# badge.net
KiCad netlist of a schematic drawn in EAGLE
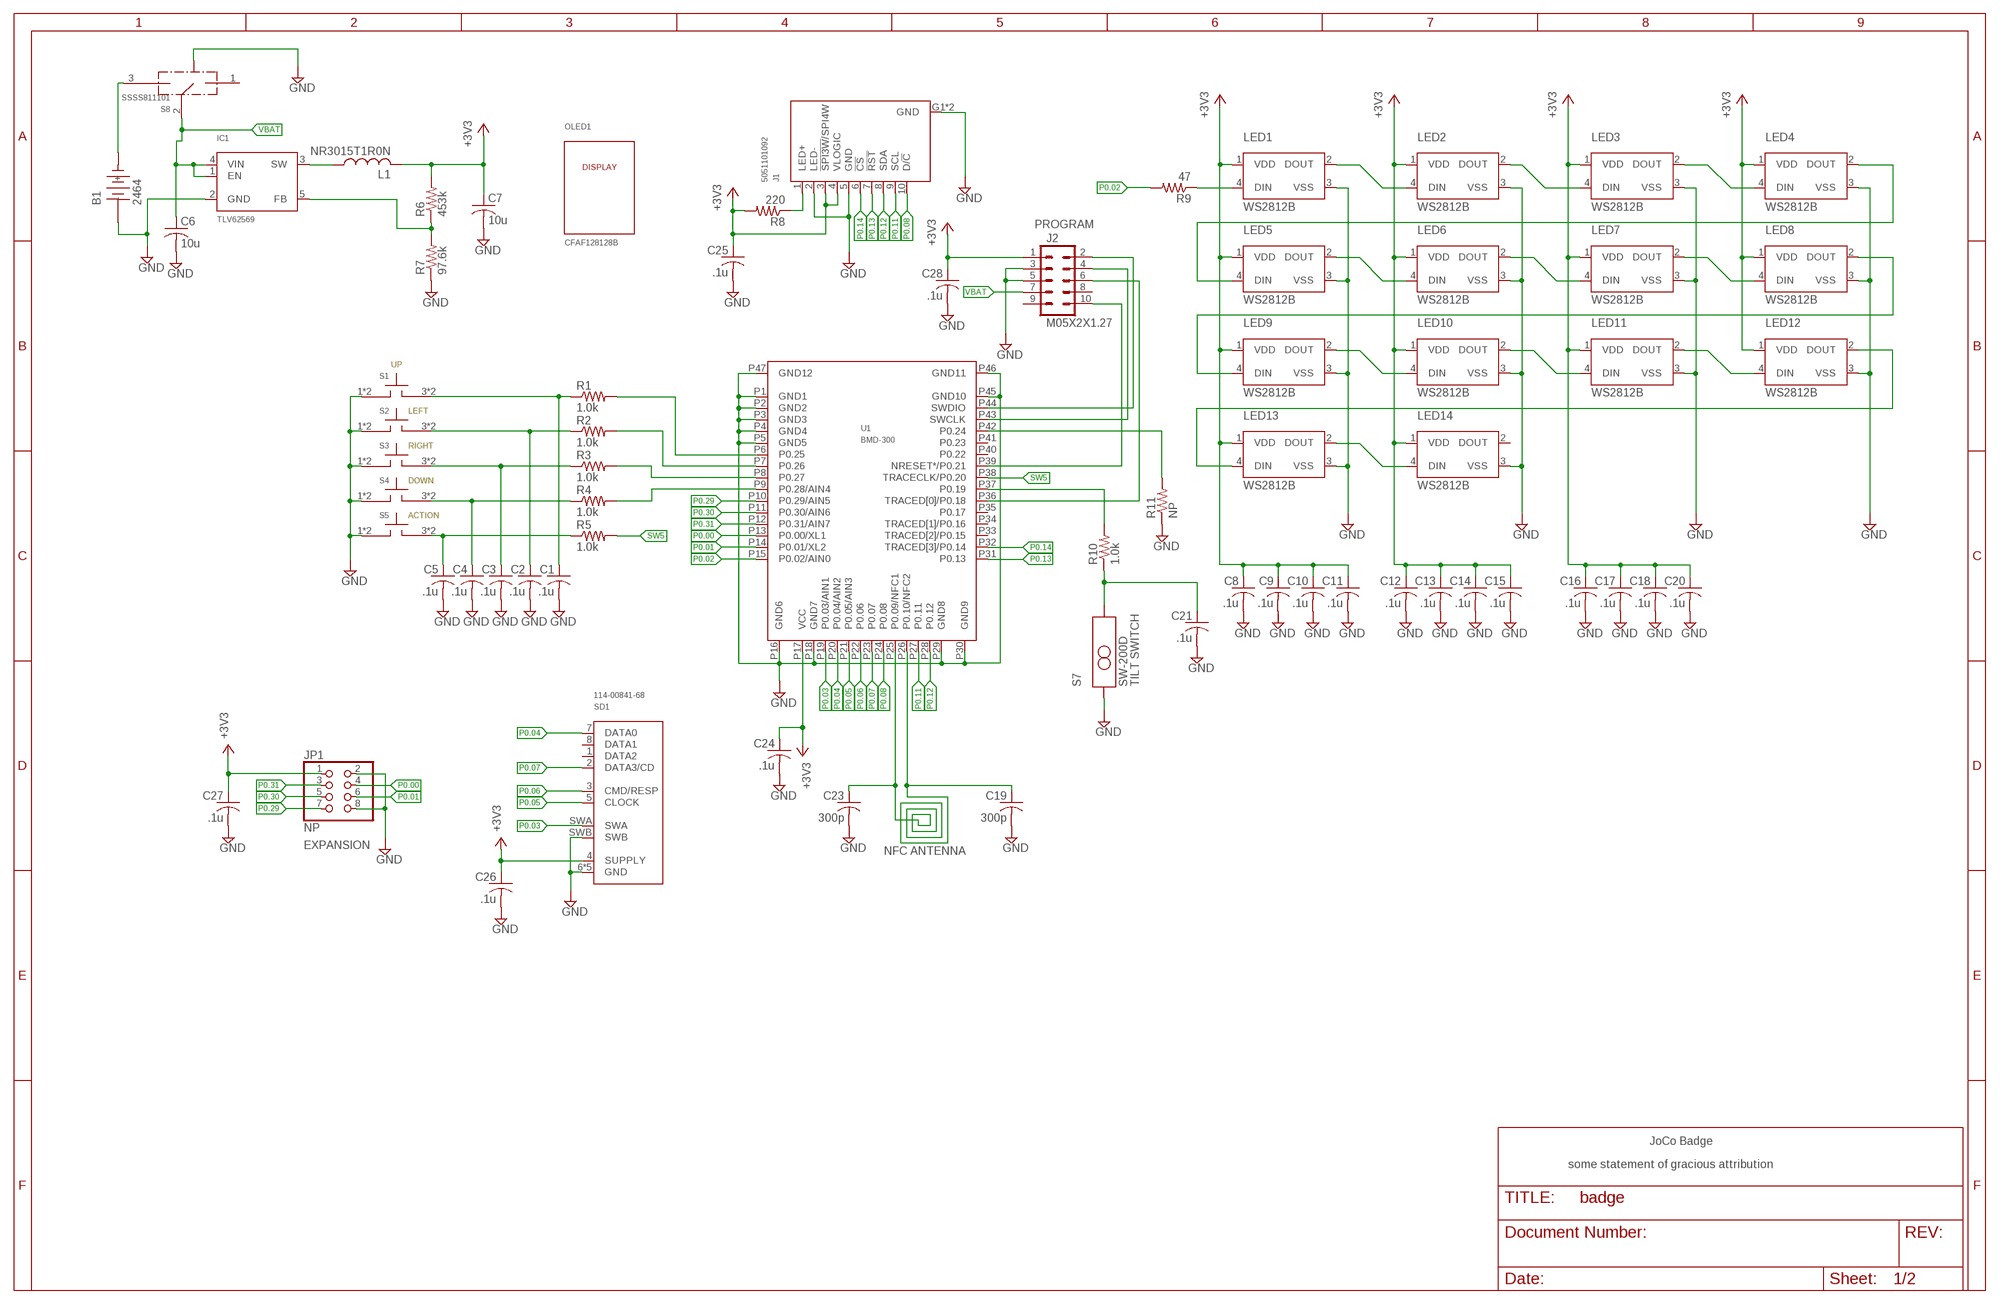
[diagram p0: schematic, sheet 1]
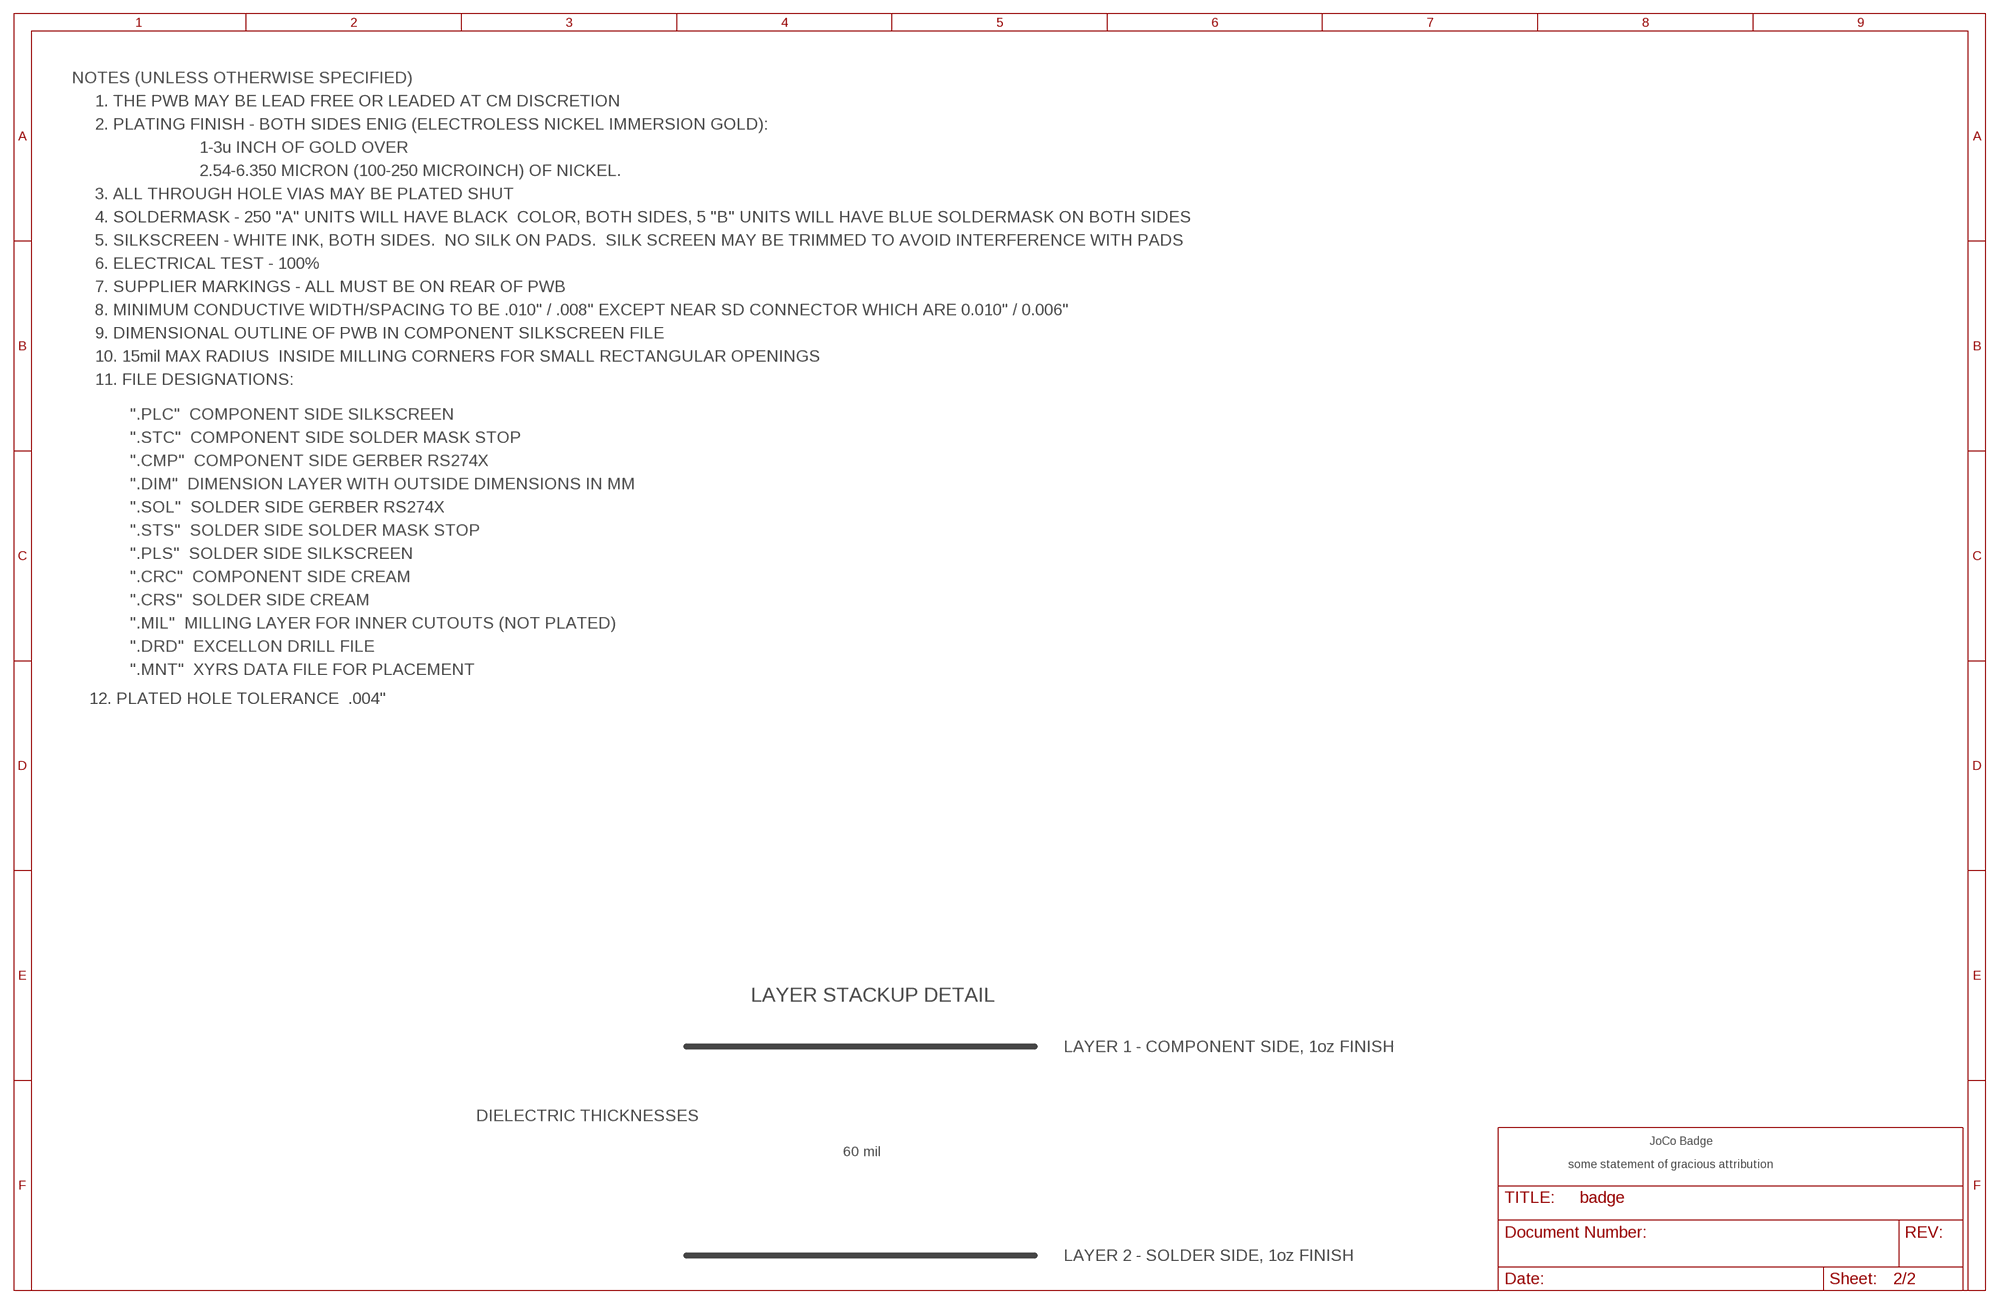
[diagram p1: schematic, sheet 2]

(export (version "E")
  (design (tool "Eeschema 10.0.6"))
  (components
    (comp (ref "B1")
      (value "2464")
      (footprint "eagle-import:2464")
      (libsource (lib "eagle-import") (part "2464"))
    )
    (comp (ref "C1")
      (value ".1u")
      (footprint "eagle-import:C0402K")
      (libsource (lib "eagle-import") (part "C-USC0402K"))
    )
    (comp (ref "C2")
      (value ".1u")
      (footprint "eagle-import:C0402K")
      (libsource (lib "eagle-import") (part "C-USC0402K"))
    )
    (comp (ref "C3")
      (value ".1u")
      (footprint "eagle-import:C0402K")
      (libsource (lib "eagle-import") (part "C-USC0402K"))
    )
    (comp (ref "C4")
      (value ".1u")
      (footprint "eagle-import:C0402K")
      (libsource (lib "eagle-import") (part "C-USC0402K"))
    )
    (comp (ref "C5")
      (value ".1u")
      (footprint "eagle-import:C0402K")
      (libsource (lib "eagle-import") (part "C-USC0402K"))
    )
    (comp (ref "C6")
      (value "10u")
      (footprint "eagle-import:C0805K")
      (fields (field (name "MPN") "JMK212BJ106KD-T"))
      (libsource (lib "eagle-import") (part "C-USC0805K"))
    )
    (comp (ref "C7")
      (value "10u")
      (footprint "eagle-import:C0805K")
      (fields (field (name "MPN") "JMK212BJ106KD-T"))
      (libsource (lib "eagle-import") (part "C-USC0805K"))
    )
    (comp (ref "C8")
      (value ".1u")
      (footprint "eagle-import:C0402K")
      (libsource (lib "eagle-import") (part "C-USC0402K"))
    )
    (comp (ref "C9")
      (value ".1u")
      (footprint "eagle-import:C0402K")
      (libsource (lib "eagle-import") (part "C-USC0402K"))
    )
    (comp (ref "C10")
      (value ".1u")
      (footprint "eagle-import:C0402K")
      (libsource (lib "eagle-import") (part "C-USC0402K"))
    )
    (comp (ref "C11")
      (value ".1u")
      (footprint "eagle-import:C0402K")
      (libsource (lib "eagle-import") (part "C-USC0402K"))
    )
    (comp (ref "C12")
      (value ".1u")
      (footprint "eagle-import:C0402K")
      (libsource (lib "eagle-import") (part "C-USC0402K"))
    )
    (comp (ref "C13")
      (value ".1u")
      (footprint "eagle-import:C0402K")
      (libsource (lib "eagle-import") (part "C-USC0402K"))
    )
    (comp (ref "C14")
      (value ".1u")
      (footprint "eagle-import:C0402K")
      (libsource (lib "eagle-import") (part "C-USC0402K"))
    )
    (comp (ref "C15")
      (value ".1u")
      (footprint "eagle-import:C0402K")
      (libsource (lib "eagle-import") (part "C-USC0402K"))
    )
    (comp (ref "C16")
      (value ".1u")
      (footprint "eagle-import:C0402K")
      (libsource (lib "eagle-import") (part "C-USC0402K"))
    )
    (comp (ref "C17")
      (value ".1u")
      (footprint "eagle-import:C0402K")
      (libsource (lib "eagle-import") (part "C-USC0402K"))
    )
    (comp (ref "C18")
      (value ".1u")
      (footprint "eagle-import:C0402K")
      (libsource (lib "eagle-import") (part "C-USC0402K"))
    )
    (comp (ref "C19")
      (value "300p")
      (footprint "eagle-import:C0603K")
      (libsource (lib "eagle-import") (part "C-USC0603K"))
    )
    (comp (ref "C20")
      (value ".1u")
      (footprint "eagle-import:C0402K")
      (libsource (lib "eagle-import") (part "C-USC0402K"))
    )
    (comp (ref "C21")
      (value ".1u")
      (footprint "eagle-import:C0402K")
      (libsource (lib "eagle-import") (part "C-USC0402K"))
    )
    (comp (ref "C23")
      (value "300p")
      (footprint "eagle-import:C0603K")
      (libsource (lib "eagle-import") (part "C-USC0603K"))
    )
    (comp (ref "C24")
      (value ".1u")
      (footprint "eagle-import:C0402K")
      (libsource (lib "eagle-import") (part "C-USC0402K"))
    )
    (comp (ref "C25")
      (value ".1u")
      (footprint "eagle-import:C0402K")
      (libsource (lib "eagle-import") (part "C-USC0402K"))
    )
    (comp (ref "C26")
      (value ".1u")
      (footprint "eagle-import:C0402K")
      (libsource (lib "eagle-import") (part "C-USC0402K"))
    )
    (comp (ref "C27")
      (value ".1u")
      (footprint "eagle-import:C0402K")
      (libsource (lib "eagle-import") (part "C-USC0402K"))
    )
    (comp (ref "C28")
      (value ".1u")
      (footprint "eagle-import:C0402K")
      (libsource (lib "eagle-import") (part "C-USC0402K"))
    )
    (comp (ref "IC1")
      (value "TLV62569")
      (footprint "eagle-import:DBV-5")
      (libsource (lib "eagle-import") (part "TLV62569"))
    )
    (comp (ref "J1")
      (value "5051101092")
      (footprint "eagle-import:5051101092")
      (libsource (lib "eagle-import") (part "5051101092"))
    )
    (comp (ref "J2")
      (value "M05X2X1.27")
      (footprint "eagle-import:2X5X1.27")
      (libsource (lib "eagle-import") (part "M05X2X1.27"))
    )
    (comp (ref "JP1")
      (value "NP")
      (footprint "eagle-import:2X04")
      (libsource (lib "eagle-import") (part "PINHD-2X4"))
    )
    (comp (ref "L1")
      (value "NR3015T1R0N")
      (footprint "eagle-import:NR3015")
      (libsource (lib "eagle-import") (part "NR3015"))
    )
    (comp (ref "LED1")
      (value "WS2812B")
      (footprint "eagle-import:WS2812B")
      (libsource (lib "eagle-import") (part "WS2812B"))
    )
    (comp (ref "LED2")
      (value "WS2812B")
      (footprint "eagle-import:WS2812B")
      (libsource (lib "eagle-import") (part "WS2812B"))
    )
    (comp (ref "LED3")
      (value "WS2812B")
      (footprint "eagle-import:WS2812B")
      (libsource (lib "eagle-import") (part "WS2812B"))
    )
    (comp (ref "LED4")
      (value "WS2812B")
      (footprint "eagle-import:WS2812B")
      (libsource (lib "eagle-import") (part "WS2812B"))
    )
    (comp (ref "LED5")
      (value "WS2812B")
      (footprint "eagle-import:WS2812B")
      (libsource (lib "eagle-import") (part "WS2812B"))
    )
    (comp (ref "LED6")
      (value "WS2812B")
      (footprint "eagle-import:WS2812B")
      (libsource (lib "eagle-import") (part "WS2812B"))
    )
    (comp (ref "LED7")
      (value "WS2812B")
      (footprint "eagle-import:WS2812B")
      (libsource (lib "eagle-import") (part "WS2812B"))
    )
    (comp (ref "LED8")
      (value "WS2812B")
      (footprint "eagle-import:WS2812B")
      (libsource (lib "eagle-import") (part "WS2812B"))
    )
    (comp (ref "LED9")
      (value "WS2812B")
      (footprint "eagle-import:WS2812B")
      (libsource (lib "eagle-import") (part "WS2812B"))
    )
    (comp (ref "LED10")
      (value "WS2812B")
      (footprint "eagle-import:WS2812B")
      (libsource (lib "eagle-import") (part "WS2812B"))
    )
    (comp (ref "LED11")
      (value "WS2812B")
      (footprint "eagle-import:WS2812B")
      (libsource (lib "eagle-import") (part "WS2812B"))
    )
    (comp (ref "LED12")
      (value "WS2812B")
      (footprint "eagle-import:WS2812B")
      (libsource (lib "eagle-import") (part "WS2812B"))
    )
    (comp (ref "LED13")
      (value "WS2812B")
      (footprint "eagle-import:WS2812B")
      (libsource (lib "eagle-import") (part "WS2812B"))
    )
    (comp (ref "LED14")
      (value "WS2812B")
      (footprint "eagle-import:WS2812B")
      (libsource (lib "eagle-import") (part "WS2812B"))
    )
    (comp (ref "OLED1")
      (value "CFAF128128B")
      (footprint "eagle-import:CFAF128128B")
      (libsource (lib "eagle-import") (part "CFAF128128B"))
    )
    (comp (ref "R1")
      (value "1.0k")
      (footprint "eagle-import:R0603")
      (libsource (lib "eagle-import") (part "R-US_R0603"))
    )
    (comp (ref "R2")
      (value "1.0k")
      (footprint "eagle-import:R0603")
      (libsource (lib "eagle-import") (part "R-US_R0603"))
    )
    (comp (ref "R3")
      (value "1.0k")
      (footprint "eagle-import:R0603")
      (libsource (lib "eagle-import") (part "R-US_R0603"))
    )
    (comp (ref "R4")
      (value "1.0k")
      (footprint "eagle-import:R0603")
      (libsource (lib "eagle-import") (part "R-US_R0603"))
    )
    (comp (ref "R5")
      (value "1.0k")
      (footprint "eagle-import:R0603")
      (libsource (lib "eagle-import") (part "R-US_R0603"))
    )
    (comp (ref "R6")
      (value "453k")
      (footprint "eagle-import:R0603")
      (libsource (lib "eagle-import") (part "R-US_R0603"))
    )
    (comp (ref "R7")
      (value "97.6k")
      (footprint "eagle-import:R0603")
      (libsource (lib "eagle-import") (part "R-US_R0603"))
    )
    (comp (ref "R8")
      (value "220")
      (footprint "eagle-import:R0603")
      (libsource (lib "eagle-import") (part "R-US_R0603"))
    )
    (comp (ref "R9")
      (value "47")
      (footprint "eagle-import:R0603")
      (libsource (lib "eagle-import") (part "R-US_R0603"))
    )
    (comp (ref "R10")
      (value "1.0k")
      (footprint "eagle-import:R0603")
      (libsource (lib "eagle-import") (part "R-US_R0603"))
    )
    (comp (ref "R11")
      (value "NP")
      (footprint "eagle-import:R0805")
      (libsource (lib "eagle-import") (part "R-US_R0805"))
    )
    (comp (ref "S1")
      (value "PTS810")
      (footprint "eagle-import:PTS810")
      (libsource (lib "eagle-import") (part "PTS810"))
    )
    (comp (ref "S2")
      (value "PTS810")
      (footprint "eagle-import:PTS810")
      (libsource (lib "eagle-import") (part "PTS810"))
    )
    (comp (ref "S3")
      (value "PTS810")
      (footprint "eagle-import:PTS810")
      (libsource (lib "eagle-import") (part "PTS810"))
    )
    (comp (ref "S4")
      (value "PTS810")
      (footprint "eagle-import:PTS810")
      (libsource (lib "eagle-import") (part "PTS810"))
    )
    (comp (ref "S5")
      (value "PTS810")
      (footprint "eagle-import:PTS810")
      (libsource (lib "eagle-import") (part "PTS810"))
    )
    (comp (ref "S7")
      (value "SW-200D")
      (footprint "eagle-import:SW-200D")
      (libsource (lib "eagle-import") (part "SW-200D"))
    )
    (comp (ref "S8")
      (value "SSSS811101")
      (footprint "eagle-import:SSSS811101")
      (libsource (lib "eagle-import") (part "SSSS811101"))
    )
    (comp (ref "SD1")
      (value "114-00841-68")
      (footprint "eagle-import:114-00841-68")
      (libsource (lib "eagle-import") (part "114-00841-68"))
    )
    (comp (ref "U1")
      (value "BMD-300")
      (footprint "eagle-import:BMD-300")
      (libsource (lib "eagle-import") (part "BMD-300"))
    )
  )
  (nets
    (net (code "1") (name "+3V3") (class "Default")
      (node (ref "C10") (pin "1") (pinfunction "1_1") (pintype "passive"))
      (node (ref "C11") (pin "1") (pinfunction "1_1") (pintype "passive"))
      (node (ref "C12") (pin "1") (pinfunction "1_1") (pintype "passive"))
      (node (ref "C13") (pin "1") (pinfunction "1_1") (pintype "passive"))
      (node (ref "C14") (pin "1") (pinfunction "1_1") (pintype "passive"))
      (node (ref "C15") (pin "1") (pinfunction "1_1") (pintype "passive"))
      (node (ref "C16") (pin "1") (pinfunction "1_1") (pintype "passive"))
      (node (ref "C17") (pin "1") (pinfunction "1_1") (pintype "passive"))
      (node (ref "C18") (pin "1") (pinfunction "1_1") (pintype "passive"))
      (node (ref "C20") (pin "1") (pinfunction "1_1") (pintype "passive"))
      (node (ref "C24") (pin "1") (pinfunction "1_1") (pintype "passive"))
      (node (ref "C25") (pin "1") (pinfunction "1_1") (pintype "passive"))
      (node (ref "C26") (pin "1") (pinfunction "1_1") (pintype "passive"))
      (node (ref "C27") (pin "1") (pinfunction "1_1") (pintype "passive"))
      (node (ref "C28") (pin "1") (pinfunction "1_1") (pintype "passive"))
      (node (ref "C7") (pin "1") (pinfunction "1_1") (pintype "passive"))
      (node (ref "C8") (pin "1") (pinfunction "1_1") (pintype "passive"))
      (node (ref "C9") (pin "1") (pinfunction "1_1") (pintype "passive"))
      (node (ref "J1") (pin "3") (pinfunction "~{SPI3W}/SPI4W_3") (pintype "bidirectional"))
      (node (ref "J1") (pin "4") (pinfunction "VLOGIC_4") (pintype "bidirectional"))
      (node (ref "J2") (pin "1") (pinfunction "1_1") (pintype "passive"))
      (node (ref "JP1") (pin "1") (pinfunction "1_1") (pintype "passive"))
      (node (ref "L1") (pin "2") (pinfunction "2_2") (pintype "passive"))
      (node (ref "LED1") (pin "1") (pinfunction "VDD_1") (pintype "bidirectional"))
      (node (ref "LED10") (pin "1") (pinfunction "VDD_1") (pintype "bidirectional"))
      (node (ref "LED11") (pin "1") (pinfunction "VDD_1") (pintype "bidirectional"))
      (node (ref "LED12") (pin "1") (pinfunction "VDD_1") (pintype "bidirectional"))
      (node (ref "LED13") (pin "1") (pinfunction "VDD_1") (pintype "bidirectional"))
      (node (ref "LED14") (pin "1") (pinfunction "VDD_1") (pintype "bidirectional"))
      (node (ref "LED2") (pin "1") (pinfunction "VDD_1") (pintype "bidirectional"))
      (node (ref "LED3") (pin "1") (pinfunction "VDD_1") (pintype "bidirectional"))
      (node (ref "LED4") (pin "1") (pinfunction "VDD_1") (pintype "bidirectional"))
      (node (ref "LED5") (pin "1") (pinfunction "VDD_1") (pintype "bidirectional"))
      (node (ref "LED6") (pin "1") (pinfunction "VDD_1") (pintype "bidirectional"))
      (node (ref "LED7") (pin "1") (pinfunction "VDD_1") (pintype "bidirectional"))
      (node (ref "LED8") (pin "1") (pinfunction "VDD_1") (pintype "bidirectional"))
      (node (ref "LED9") (pin "1") (pinfunction "VDD_1") (pintype "bidirectional"))
      (node (ref "R6") (pin "2") (pinfunction "2_2") (pintype "passive"))
      (node (ref "R8") (pin "2") (pinfunction "2_2") (pintype "passive"))
      (node (ref "SD1") (pin "4") (pinfunction "SUPPLY_4") (pintype "bidirectional"))
      (node (ref "U1") (pin "P17") (pinfunction "VCC_P17") (pintype "bidirectional"))
    )
    (net (code "2") (name "GND") (class "Default")
      (node (ref "B1") (pin "-") (pinfunction "-_-") (pintype "bidirectional"))
      (node (ref "C1") (pin "2") (pinfunction "2_2") (pintype "passive"))
      (node (ref "C10") (pin "2") (pinfunction "2_2") (pintype "passive"))
      (node (ref "C11") (pin "2") (pinfunction "2_2") (pintype "passive"))
      (node (ref "C12") (pin "2") (pinfunction "2_2") (pintype "passive"))
      (node (ref "C13") (pin "2") (pinfunction "2_2") (pintype "passive"))
      (node (ref "C14") (pin "2") (pinfunction "2_2") (pintype "passive"))
      (node (ref "C15") (pin "2") (pinfunction "2_2") (pintype "passive"))
      (node (ref "C16") (pin "2") (pinfunction "2_2") (pintype "passive"))
      (node (ref "C17") (pin "2") (pinfunction "2_2") (pintype "passive"))
      (node (ref "C18") (pin "2") (pinfunction "2_2") (pintype "passive"))
      (node (ref "C19") (pin "2") (pinfunction "2_2") (pintype "passive"))
      (node (ref "C2") (pin "2") (pinfunction "2_2") (pintype "passive"))
      (node (ref "C20") (pin "2") (pinfunction "2_2") (pintype "passive"))
      (node (ref "C21") (pin "2") (pinfunction "2_2") (pintype "passive"))
      (node (ref "C23") (pin "2") (pinfunction "2_2") (pintype "passive"))
      (node (ref "C24") (pin "2") (pinfunction "2_2") (pintype "passive"))
      (node (ref "C25") (pin "2") (pinfunction "2_2") (pintype "passive"))
      (node (ref "C26") (pin "2") (pinfunction "2_2") (pintype "passive"))
      (node (ref "C27") (pin "2") (pinfunction "2_2") (pintype "passive"))
      (node (ref "C28") (pin "2") (pinfunction "2_2") (pintype "passive"))
      (node (ref "C3") (pin "2") (pinfunction "2_2") (pintype "passive"))
      (node (ref "C4") (pin "2") (pinfunction "2_2") (pintype "passive"))
      (node (ref "C5") (pin "2") (pinfunction "2_2") (pintype "passive"))
      (node (ref "C6") (pin "2") (pinfunction "2_2") (pintype "passive"))
      (node (ref "C7") (pin "2") (pinfunction "2_2") (pintype "passive"))
      (node (ref "C8") (pin "2") (pinfunction "2_2") (pintype "passive"))
      (node (ref "C9") (pin "2") (pinfunction "2_2") (pintype "passive"))
      (node (ref "IC1") (pin "2") (pinfunction "GND_2") (pintype "bidirectional"))
      (node (ref "J1") (pin "2") (pinfunction "LED-_2") (pintype "bidirectional"))
      (node (ref "J1") (pin "5") (pinfunction "GND_5") (pintype "bidirectional"))
      (node (ref "J1") (pin "G1") (pinfunction "GND_G1") (pintype "bidirectional"))
      (node (ref "J1") (pin "G2") (pinfunction "GND_G2") (pintype "bidirectional"))
      (node (ref "J2") (pin "3") (pinfunction "3_3") (pintype "passive"))
      (node (ref "J2") (pin "5") (pinfunction "5_5") (pintype "passive"))
      (node (ref "JP1") (pin "2") (pinfunction "2_2") (pintype "passive"))
      (node (ref "JP1") (pin "8") (pinfunction "8_8") (pintype "passive"))
      (node (ref "LED1") (pin "3") (pinfunction "VSS_3") (pintype "bidirectional"))
      (node (ref "LED10") (pin "3") (pinfunction "VSS_3") (pintype "bidirectional"))
      (node (ref "LED11") (pin "3") (pinfunction "VSS_3") (pintype "bidirectional"))
      (node (ref "LED12") (pin "3") (pinfunction "VSS_3") (pintype "bidirectional"))
      (node (ref "LED13") (pin "3") (pinfunction "VSS_3") (pintype "bidirectional"))
      (node (ref "LED14") (pin "3") (pinfunction "VSS_3") (pintype "bidirectional"))
      (node (ref "LED2") (pin "3") (pinfunction "VSS_3") (pintype "bidirectional"))
      (node (ref "LED3") (pin "3") (pinfunction "VSS_3") (pintype "bidirectional"))
      (node (ref "LED4") (pin "3") (pinfunction "VSS_3") (pintype "bidirectional"))
      (node (ref "LED5") (pin "3") (pinfunction "VSS_3") (pintype "bidirectional"))
      (node (ref "LED6") (pin "3") (pinfunction "VSS_3") (pintype "bidirectional"))
      (node (ref "LED7") (pin "3") (pinfunction "VSS_3") (pintype "bidirectional"))
      (node (ref "LED8") (pin "3") (pinfunction "VSS_3") (pintype "bidirectional"))
      (node (ref "LED9") (pin "3") (pinfunction "VSS_3") (pintype "bidirectional"))
      (node (ref "R11") (pin "1") (pinfunction "1_1") (pintype "passive"))
      (node (ref "R7") (pin "1") (pinfunction "1_1") (pintype "passive"))
      (node (ref "S1") (pin "1") (pinfunction "A_1") (pintype "bidirectional"))
      (node (ref "S1") (pin "2") (pinfunction "A_2") (pintype "bidirectional"))
      (node (ref "S2") (pin "1") (pinfunction "A_1") (pintype "bidirectional"))
      (node (ref "S2") (pin "2") (pinfunction "A_2") (pintype "bidirectional"))
      (node (ref "S3") (pin "1") (pinfunction "A_1") (pintype "bidirectional"))
      (node (ref "S3") (pin "2") (pinfunction "A_2") (pintype "bidirectional"))
      (node (ref "S4") (pin "1") (pinfunction "A_1") (pintype "bidirectional"))
      (node (ref "S4") (pin "2") (pinfunction "A_2") (pintype "bidirectional"))
      (node (ref "S5") (pin "1") (pinfunction "A_1") (pintype "bidirectional"))
      (node (ref "S5") (pin "2") (pinfunction "A_2") (pintype "bidirectional"))
      (node (ref "S7") (pin "A") (pinfunction "P$1_A") (pintype "bidirectional"))
      (node (ref "S8") (pin "G1") (pinfunction "GND_G1") (pintype "bidirectional"))
      (node (ref "S8") (pin "G2") (pinfunction "GND_G2") (pintype "bidirectional"))
      (node (ref "S8") (pin "G3") (pinfunction "GND_G3") (pintype "bidirectional"))
      (node (ref "S8") (pin "G4") (pinfunction "GND_G4") (pintype "bidirectional"))
      (node (ref "SD1") (pin "6") (pinfunction "GND_6") (pintype "bidirectional"))
      (node (ref "SD1") (pin "G1") (pinfunction "GND_G1") (pintype "bidirectional"))
      (node (ref "SD1") (pin "G2") (pinfunction "GND_G2") (pintype "bidirectional"))
      (node (ref "SD1") (pin "G3") (pinfunction "GND_G3") (pintype "bidirectional"))
      (node (ref "SD1") (pin "G4") (pinfunction "GND_G4") (pintype "bidirectional"))
      (node (ref "SD1") (pin "SWB") (pinfunction "SWB_SWB") (pintype "bidirectional"))
      (node (ref "U1") (pin "P1") (pinfunction "GND1_P1") (pintype "bidirectional"))
      (node (ref "U1") (pin "P16") (pinfunction "GND6_P16") (pintype "bidirectional"))
      (node (ref "U1") (pin "P18") (pinfunction "GND7_P18") (pintype "bidirectional"))
      (node (ref "U1") (pin "P2") (pinfunction "GND2_P2") (pintype "bidirectional"))
      (node (ref "U1") (pin "P29") (pinfunction "GND8_P29") (pintype "bidirectional"))
      (node (ref "U1") (pin "P3") (pinfunction "GND3_P3") (pintype "bidirectional"))
      (node (ref "U1") (pin "P30") (pinfunction "GND9_P30") (pintype "bidirectional"))
      (node (ref "U1") (pin "P4") (pinfunction "GND4_P4") (pintype "bidirectional"))
      (node (ref "U1") (pin "P45") (pinfunction "GND10_P45") (pintype "bidirectional"))
      (node (ref "U1") (pin "P46") (pinfunction "GND11_P46") (pintype "bidirectional"))
      (node (ref "U1") (pin "P47") (pinfunction "GND12_P47") (pintype "bidirectional"))
      (node (ref "U1") (pin "P5") (pinfunction "GND5_P5") (pintype "bidirectional"))
    )
    (net (code "3") (name "Net-(B1-Pad+)") (class "Default")
      (node (ref "B1") (pin "+") (pinfunction "+_+") (pintype "bidirectional"))
      (node (ref "S8") (pin "3") (pinfunction "3_3") (pintype "bidirectional"))
    )
    (net (code "4") (name "Net-(C1-Pad1)") (class "Default")
      (node (ref "C1") (pin "1") (pinfunction "1_1") (pintype "passive"))
      (node (ref "R1") (pin "1") (pinfunction "1_1") (pintype "passive"))
      (node (ref "S1") (pin "3") (pinfunction "B_3") (pintype "bidirectional"))
      (node (ref "S1") (pin "4") (pinfunction "B_4") (pintype "bidirectional"))
    )
    (net (code "5") (name "Net-(C2-Pad1)") (class "Default")
      (node (ref "C2") (pin "1") (pinfunction "1_1") (pintype "passive"))
      (node (ref "R2") (pin "1") (pinfunction "1_1") (pintype "passive"))
      (node (ref "S2") (pin "3") (pinfunction "B_3") (pintype "bidirectional"))
      (node (ref "S2") (pin "4") (pinfunction "B_4") (pintype "bidirectional"))
    )
    (net (code "6") (name "Net-(C3-Pad1)") (class "Default")
      (node (ref "C3") (pin "1") (pinfunction "1_1") (pintype "passive"))
      (node (ref "R3") (pin "1") (pinfunction "1_1") (pintype "passive"))
      (node (ref "S3") (pin "3") (pinfunction "B_3") (pintype "bidirectional"))
      (node (ref "S3") (pin "4") (pinfunction "B_4") (pintype "bidirectional"))
    )
    (net (code "7") (name "Net-(C4-Pad1)") (class "Default")
      (node (ref "C4") (pin "1") (pinfunction "1_1") (pintype "passive"))
      (node (ref "R4") (pin "1") (pinfunction "1_1") (pintype "passive"))
      (node (ref "S4") (pin "3") (pinfunction "B_3") (pintype "bidirectional"))
      (node (ref "S4") (pin "4") (pinfunction "B_4") (pintype "bidirectional"))
    )
    (net (code "8") (name "Net-(C5-Pad1)") (class "Default")
      (node (ref "C5") (pin "1") (pinfunction "1_1") (pintype "passive"))
      (node (ref "R5") (pin "1") (pinfunction "1_1") (pintype "passive"))
      (node (ref "S5") (pin "3") (pinfunction "B_3") (pintype "bidirectional"))
      (node (ref "S5") (pin "4") (pinfunction "B_4") (pintype "bidirectional"))
    )
    (net (code "9") (name "Net-(IC1-FB)") (class "Default")
      (node (ref "IC1") (pin "5") (pinfunction "FB_5") (pintype "bidirectional"))
      (node (ref "R6") (pin "1") (pinfunction "1_1") (pintype "passive"))
      (node (ref "R7") (pin "2") (pinfunction "2_2") (pintype "passive"))
    )
    (net (code "10") (name "Net-(IC1-SW)") (class "Default")
      (node (ref "IC1") (pin "3") (pinfunction "SW_3") (pintype "bidirectional"))
      (node (ref "L1") (pin "1") (pinfunction "1_1") (pintype "passive"))
    )
    (net (code "11") (name "Net-(J1-LED+)") (class "Default")
      (node (ref "J1") (pin "1") (pinfunction "LED+_1") (pintype "bidirectional"))
      (node (ref "R8") (pin "1") (pinfunction "1_1") (pintype "passive"))
    )
    (net (code "12") (name "Net-(LED1-DIN)") (class "Default")
      (node (ref "LED1") (pin "4") (pinfunction "DIN_4") (pintype "bidirectional"))
      (node (ref "R9") (pin "1") (pinfunction "1_1") (pintype "passive"))
    )
    (net (code "13") (name "Net-(LED1-DOUT)") (class "Default")
      (node (ref "LED1") (pin "2") (pinfunction "DOUT_2") (pintype "bidirectional"))
      (node (ref "LED2") (pin "4") (pinfunction "DIN_4") (pintype "bidirectional"))
    )
    (net (code "14") (name "Net-(LED2-DOUT)") (class "Default")
      (node (ref "LED2") (pin "2") (pinfunction "DOUT_2") (pintype "bidirectional"))
      (node (ref "LED3") (pin "4") (pinfunction "DIN_4") (pintype "bidirectional"))
    )
    (net (code "15") (name "Net-(LED3-DOUT)") (class "Default")
      (node (ref "LED3") (pin "2") (pinfunction "DOUT_2") (pintype "bidirectional"))
      (node (ref "LED4") (pin "4") (pinfunction "DIN_4") (pintype "bidirectional"))
    )
    (net (code "16") (name "Net-(LED4-DOUT)") (class "Default")
      (node (ref "LED4") (pin "2") (pinfunction "DOUT_2") (pintype "bidirectional"))
      (node (ref "LED5") (pin "4") (pinfunction "DIN_4") (pintype "bidirectional"))
    )
    (net (code "17") (name "Net-(LED5-DOUT)") (class "Default")
      (node (ref "LED5") (pin "2") (pinfunction "DOUT_2") (pintype "bidirectional"))
      (node (ref "LED6") (pin "4") (pinfunction "DIN_4") (pintype "bidirectional"))
    )
    (net (code "18") (name "Net-(LED6-DOUT)") (class "Default")
      (node (ref "LED6") (pin "2") (pinfunction "DOUT_2") (pintype "bidirectional"))
      (node (ref "LED7") (pin "4") (pinfunction "DIN_4") (pintype "bidirectional"))
    )
    (net (code "19") (name "Net-(LED7-DOUT)") (class "Default")
      (node (ref "LED7") (pin "2") (pinfunction "DOUT_2") (pintype "bidirectional"))
      (node (ref "LED8") (pin "4") (pinfunction "DIN_4") (pintype "bidirectional"))
    )
    (net (code "20") (name "Net-(LED8-DOUT)") (class "Default")
      (node (ref "LED8") (pin "2") (pinfunction "DOUT_2") (pintype "bidirectional"))
      (node (ref "LED9") (pin "4") (pinfunction "DIN_4") (pintype "bidirectional"))
    )
    (net (code "21") (name "Net-(LED10-DIN)") (class "Default")
      (node (ref "LED10") (pin "4") (pinfunction "DIN_4") (pintype "bidirectional"))
      (node (ref "LED9") (pin "2") (pinfunction "DOUT_2") (pintype "bidirectional"))
    )
    (net (code "22") (name "Net-(LED10-DOUT)") (class "Default")
      (node (ref "LED10") (pin "2") (pinfunction "DOUT_2") (pintype "bidirectional"))
      (node (ref "LED11") (pin "4") (pinfunction "DIN_4") (pintype "bidirectional"))
    )
    (net (code "23") (name "Net-(LED11-DOUT)") (class "Default")
      (node (ref "LED11") (pin "2") (pinfunction "DOUT_2") (pintype "bidirectional"))
      (node (ref "LED12") (pin "4") (pinfunction "DIN_4") (pintype "bidirectional"))
    )
    (net (code "24") (name "Net-(LED12-DOUT)") (class "Default")
      (node (ref "LED12") (pin "2") (pinfunction "DOUT_2") (pintype "bidirectional"))
      (node (ref "LED13") (pin "4") (pinfunction "DIN_4") (pintype "bidirectional"))
    )
    (net (code "25") (name "Net-(LED13-DOUT)") (class "Default")
      (node (ref "LED13") (pin "2") (pinfunction "DOUT_2") (pintype "bidirectional"))
      (node (ref "LED14") (pin "4") (pinfunction "DIN_4") (pintype "bidirectional"))
    )
    (net (code "26") (name "Net-(S7-P$2)") (class "Default")
      (node (ref "C21") (pin "1") (pinfunction "1_1") (pintype "passive"))
      (node (ref "R10") (pin "1") (pinfunction "1_1") (pintype "passive"))
      (node (ref "S7") (pin "C") (pinfunction "P$2_C") (pintype "bidirectional"))
    )
    (net (code "27") (name "Net-(U1-NRESET*{slash}P0.21)") (class "Default")
      (node (ref "J2") (pin "10") (pinfunction "10_10") (pintype "passive"))
      (node (ref "U1") (pin "P39") (pinfunction "NRESET*/P0.21_P39") (pintype "bidirectional"))
    )
    (net (code "28") (name "Net-(U1-P0.09{slash}NFC1)") (class "Default")
      (node (ref "C19") (pin "1") (pinfunction "1_1") (pintype "passive"))
      (node (ref "C23") (pin "1") (pinfunction "1_1") (pintype "passive"))
      (node (ref "U1") (pin "P25") (pinfunction "P0.09/NFC1_P25") (pintype "bidirectional"))
      (node (ref "U1") (pin "P26") (pinfunction "P0.10/NFC2_P26") (pintype "bidirectional"))
    )
    (net (code "29") (name "Net-(U1-P0.19)") (class "Default")
      (node (ref "R10") (pin "2") (pinfunction "2_2") (pintype "passive"))
      (node (ref "U1") (pin "P37") (pinfunction "P0.19_P37") (pintype "bidirectional"))
    )
    (net (code "30") (name "Net-(U1-P0.24)") (class "Default")
      (node (ref "R11") (pin "2") (pinfunction "2_2") (pintype "passive"))
      (node (ref "U1") (pin "P42") (pinfunction "P0.24_P42") (pintype "bidirectional"))
    )
    (net (code "31") (name "Net-(U1-P0.25)") (class "Default")
      (node (ref "R1") (pin "2") (pinfunction "2_2") (pintype "passive"))
      (node (ref "U1") (pin "P6") (pinfunction "P0.25_P6") (pintype "bidirectional"))
    )
    (net (code "32") (name "Net-(U1-P0.26)") (class "Default")
      (node (ref "R2") (pin "2") (pinfunction "2_2") (pintype "passive"))
      (node (ref "U1") (pin "P7") (pinfunction "P0.26_P7") (pintype "bidirectional"))
    )
    (net (code "33") (name "Net-(U1-P0.27)") (class "Default")
      (node (ref "R3") (pin "2") (pinfunction "2_2") (pintype "passive"))
      (node (ref "U1") (pin "P8") (pinfunction "P0.27_P8") (pintype "bidirectional"))
    )
    (net (code "34") (name "Net-(U1-P0.28{slash}AIN4)") (class "Default")
      (node (ref "R4") (pin "2") (pinfunction "2_2") (pintype "passive"))
      (node (ref "U1") (pin "P9") (pinfunction "P0.28/AIN4_P9") (pintype "bidirectional"))
    )
    (net (code "35") (name "Net-(U1-SWCLK)") (class "Default")
      (node (ref "J2") (pin "4") (pinfunction "4_4") (pintype "passive"))
      (node (ref "U1") (pin "P43") (pinfunction "SWCLK_P43") (pintype "bidirectional"))
    )
    (net (code "36") (name "Net-(U1-SWDIO)") (class "Default")
      (node (ref "J2") (pin "2") (pinfunction "2_2") (pintype "passive"))
      (node (ref "U1") (pin "P44") (pinfunction "SWDIO_P44") (pintype "bidirectional"))
    )
    (net (code "37") (name "Net-(U1-TRACED[0]{slash}P0.18)") (class "Default")
      (node (ref "J2") (pin "6") (pinfunction "6_6") (pintype "passive"))
      (node (ref "U1") (pin "P36") (pinfunction "TRACED[0]/P0.18_P36") (pintype "bidirectional"))
    )
    (net (code "38") (name "P0.00") (class "Default")
      (node (ref "JP1") (pin "4") (pinfunction "4_4") (pintype "passive"))
      (node (ref "U1") (pin "P13") (pinfunction "P0.00/XL1_P13") (pintype "bidirectional"))
    )
    (net (code "39") (name "P0.01") (class "Default")
      (node (ref "JP1") (pin "6") (pinfunction "6_6") (pintype "passive"))
      (node (ref "U1") (pin "P14") (pinfunction "P0.01/XL2_P14") (pintype "bidirectional"))
    )
    (net (code "40") (name "P0.02") (class "Default")
      (node (ref "R9") (pin "2") (pinfunction "2_2") (pintype "passive"))
      (node (ref "U1") (pin "P15") (pinfunction "P0.02/AIN0_P15") (pintype "bidirectional"))
    )
    (net (code "41") (name "P0.03") (class "Default")
      (node (ref "SD1") (pin "SWA") (pinfunction "SWA_SWA") (pintype "bidirectional"))
      (node (ref "U1") (pin "P19") (pinfunction "P0.03/AIN1_P19") (pintype "bidirectional"))
    )
    (net (code "42") (name "P0.04") (class "Default")
      (node (ref "SD1") (pin "7") (pinfunction "DATA0_7") (pintype "bidirectional"))
      (node (ref "U1") (pin "P20") (pinfunction "P0.04/AIN2_P20") (pintype "bidirectional"))
    )
    (net (code "43") (name "P0.05") (class "Default")
      (node (ref "SD1") (pin "5") (pinfunction "CLOCK_5") (pintype "bidirectional"))
      (node (ref "U1") (pin "P21") (pinfunction "P0.05/AIN3_P21") (pintype "bidirectional"))
    )
    (net (code "44") (name "P0.06") (class "Default")
      (node (ref "SD1") (pin "3") (pinfunction "CMD/RESP_3") (pintype "bidirectional"))
      (node (ref "U1") (pin "P22") (pinfunction "P0.06_P22") (pintype "bidirectional"))
    )
    (net (code "45") (name "P0.07") (class "Default")
      (node (ref "SD1") (pin "2") (pinfunction "DATA3/CD_2") (pintype "bidirectional"))
      (node (ref "U1") (pin "P23") (pinfunction "P0.07_P23") (pintype "bidirectional"))
    )
    (net (code "46") (name "P0.08") (class "Default")
      (node (ref "J1") (pin "10") (pinfunction "D/~{C}_10") (pintype "bidirectional"))
      (node (ref "U1") (pin "P24") (pinfunction "P0.08_P24") (pintype "bidirectional"))
    )
    (net (code "47") (name "P0.11") (class "Default")
      (node (ref "J1") (pin "9") (pinfunction "SCL_9") (pintype "bidirectional"))
      (node (ref "U1") (pin "P27") (pinfunction "P0.11_P27") (pintype "bidirectional"))
    )
    (net (code "48") (name "P0.12") (class "Default")
      (node (ref "J1") (pin "8") (pinfunction "SDA_8") (pintype "bidirectional"))
      (node (ref "U1") (pin "P28") (pinfunction "P0.12_P28") (pintype "bidirectional"))
    )
    (net (code "49") (name "P0.13") (class "Default")
      (node (ref "J1") (pin "7") (pinfunction "~{RST}_7") (pintype "bidirectional"))
      (node (ref "U1") (pin "P31") (pinfunction "P0.13_P31") (pintype "bidirectional"))
    )
    (net (code "50") (name "P0.14") (class "Default")
      (node (ref "J1") (pin "6") (pinfunction "~{CS}_6") (pintype "bidirectional"))
      (node (ref "U1") (pin "P32") (pinfunction "TRACED[3]/P0.14_P32") (pintype "bidirectional"))
    )
    (net (code "51") (name "P0.29") (class "Default")
      (node (ref "JP1") (pin "7") (pinfunction "7_7") (pintype "passive"))
      (node (ref "U1") (pin "P10") (pinfunction "P0.29/AIN5_P10") (pintype "bidirectional"))
    )
    (net (code "52") (name "P0.30") (class "Default")
      (node (ref "JP1") (pin "5") (pinfunction "5_5") (pintype "passive"))
      (node (ref "U1") (pin "P11") (pinfunction "P0.30/AIN6_P11") (pintype "bidirectional"))
    )
    (net (code "53") (name "P0.31") (class "Default")
      (node (ref "JP1") (pin "3") (pinfunction "3_3") (pintype "passive"))
      (node (ref "U1") (pin "P12") (pinfunction "P0.31/AIN7_P12") (pintype "bidirectional"))
    )
    (net (code "54") (name "SW5") (class "Default")
      (node (ref "R5") (pin "2") (pinfunction "2_2") (pintype "passive"))
      (node (ref "U1") (pin "P38") (pinfunction "TRACECLK/P0.20_P38") (pintype "bidirectional"))
    )
    (net (code "55") (name "VBAT") (class "Default")
      (node (ref "C6") (pin "1") (pinfunction "1_1") (pintype "passive"))
      (node (ref "IC1") (pin "1") (pinfunction "EN_1") (pintype "bidirectional"))
      (node (ref "IC1") (pin "4") (pinfunction "VIN_4") (pintype "bidirectional"))
      (node (ref "J2") (pin "7") (pinfunction "7_7") (pintype "passive"))
      (node (ref "S8") (pin "2") (pinfunction "2_2") (pintype "bidirectional"))
    )
    (net (code "56") (name "unconnected-(J2-Pad8)") (class "Default")
      (node (ref "J2") (pin "8") (pinfunction "8_8") (pintype "passive"))
    )
    (net (code "57") (name "unconnected-(J2-Pad9)") (class "Default")
      (node (ref "J2") (pin "9") (pinfunction "9_9") (pintype "passive"))
    )
    (net (code "58") (name "unconnected-(LED14-DOUT-Pad2)") (class "Default")
      (node (ref "LED14") (pin "2") (pinfunction "DOUT_2") (pintype "bidirectional"))
    )
    (net (code "59") (name "unconnected-(S8-Pad1)") (class "Default")
      (node (ref "S8") (pin "1") (pinfunction "1_1") (pintype "bidirectional"))
    )
    (net (code "60") (name "unconnected-(SD1-DATA1-Pad8)") (class "Default")
      (node (ref "SD1") (pin "8") (pinfunction "DATA1_8") (pintype "bidirectional"))
    )
    (net (code "61") (name "unconnected-(SD1-DATA2-Pad1)") (class "Default")
      (node (ref "SD1") (pin "1") (pinfunction "DATA2_1") (pintype "bidirectional"))
    )
    (net (code "62") (name "unconnected-(U1-P0.17-PadP35)") (class "Default")
      (node (ref "U1") (pin "P35") (pinfunction "P0.17_P35") (pintype "bidirectional"))
    )
    (net (code "63") (name "unconnected-(U1-P0.22-PadP40)") (class "Default")
      (node (ref "U1") (pin "P40") (pinfunction "P0.22_P40") (pintype "bidirectional"))
    )
    (net (code "64") (name "unconnected-(U1-P0.23-PadP41)") (class "Default")
      (node (ref "U1") (pin "P41") (pinfunction "P0.23_P41") (pintype "bidirectional"))
    )
    (net (code "65") (name "unconnected-(U1-TRACED[1]{slash}P0.16-PadP34)") (class "Default")
      (node (ref "U1") (pin "P34") (pinfunction "TRACED[1]/P0.16_P34") (pintype "bidirectional"))
    )
    (net (code "66") (name "unconnected-(U1-TRACED[2]{slash}P0.15-PadP33)") (class "Default")
      (node (ref "U1") (pin "P33") (pinfunction "TRACED[2]/P0.15_P33") (pintype "bidirectional"))
    )
  )
)
